# pc_sensything_v1.net
KiCad netlist of a schematic drawn in EAGLE
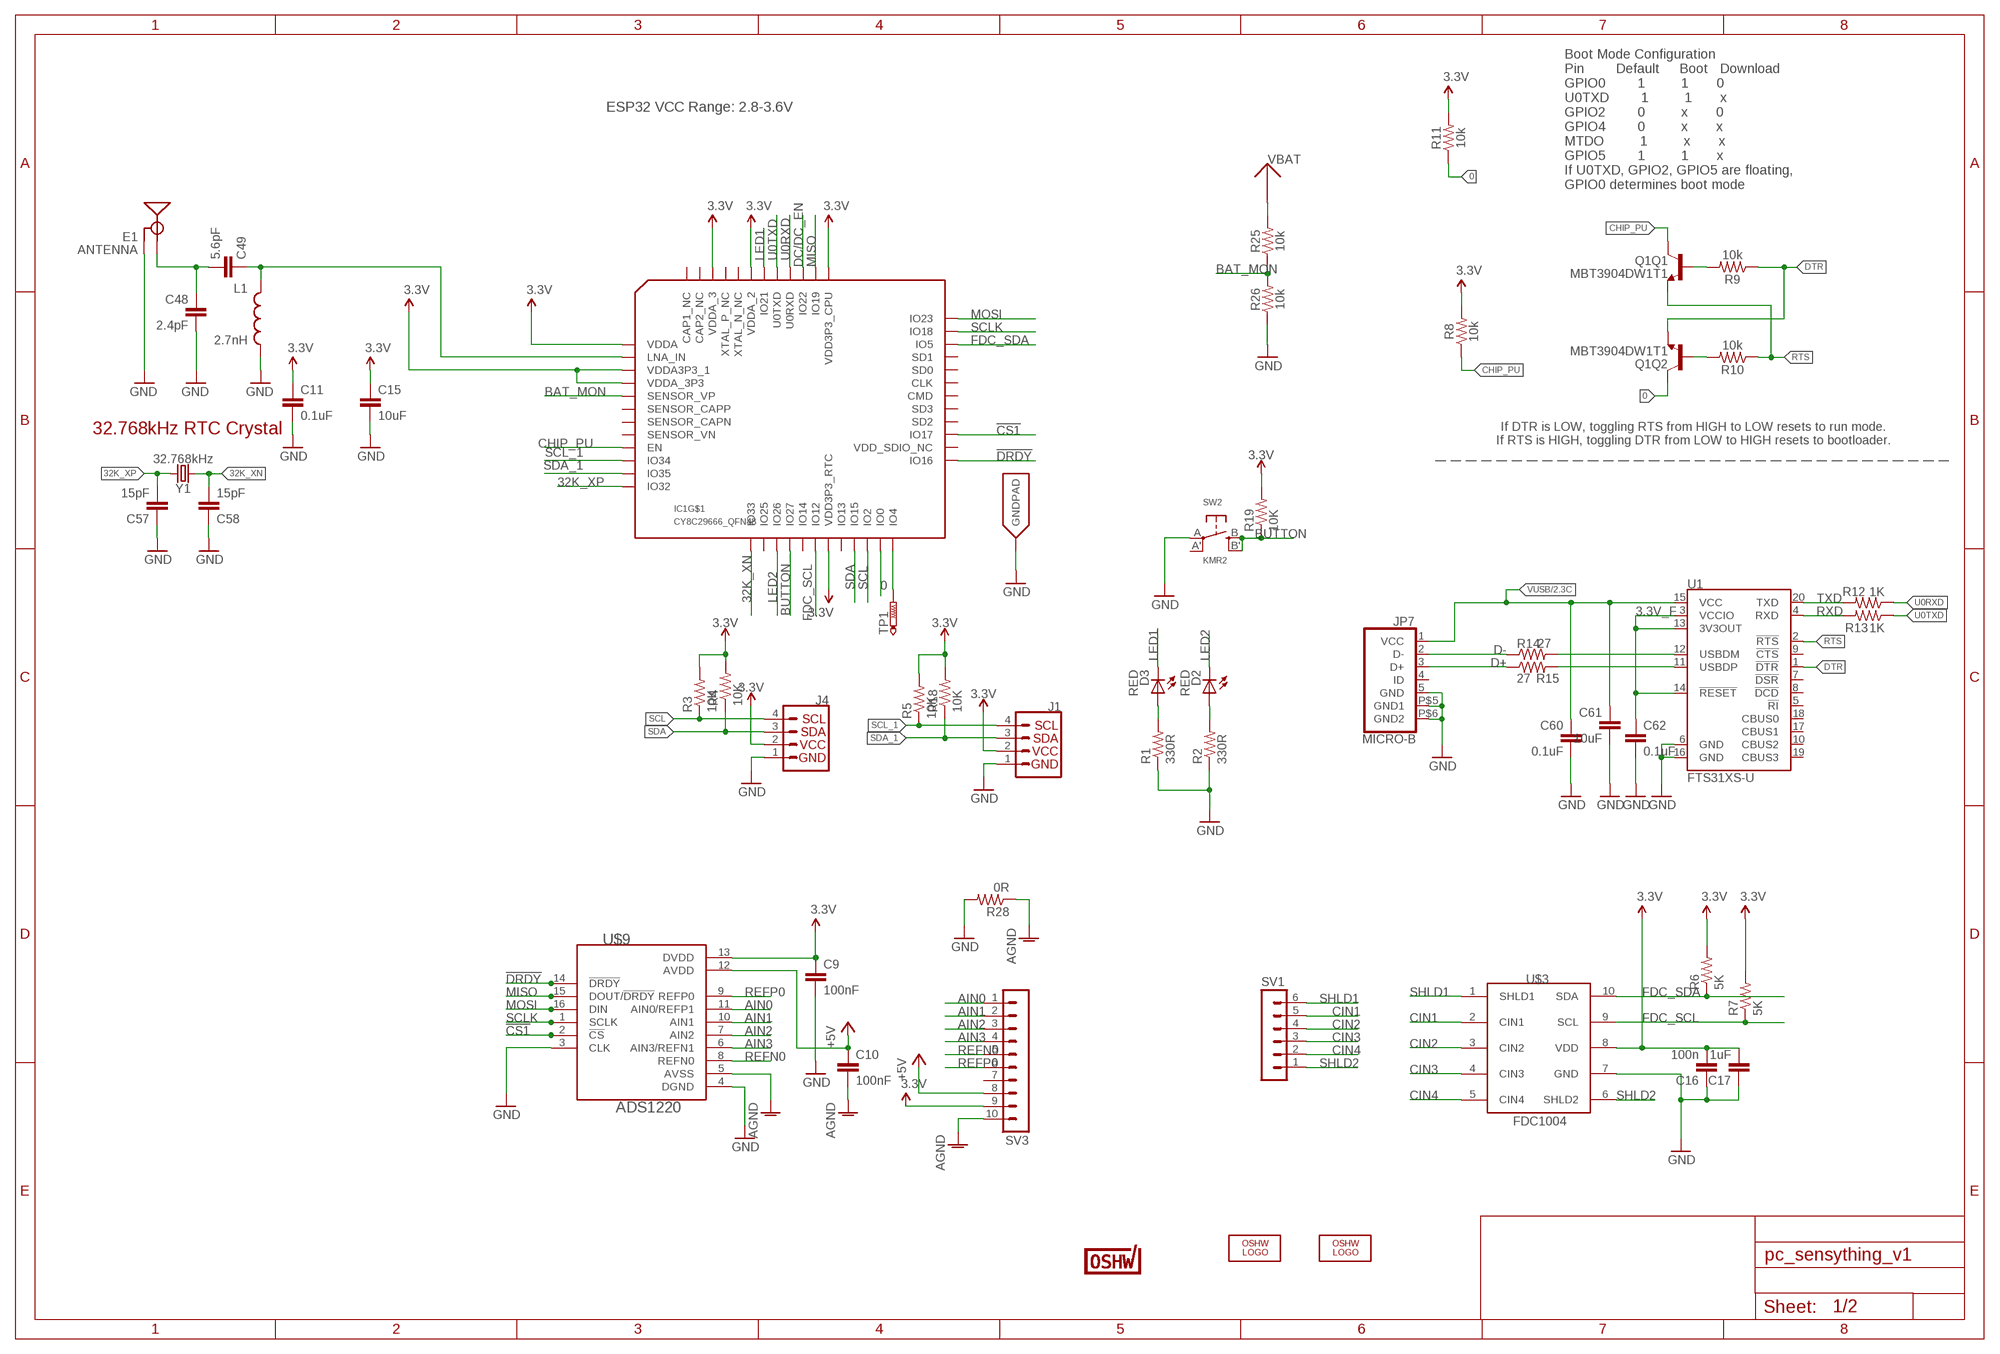
[diagram p0: schematic, sheet 1]
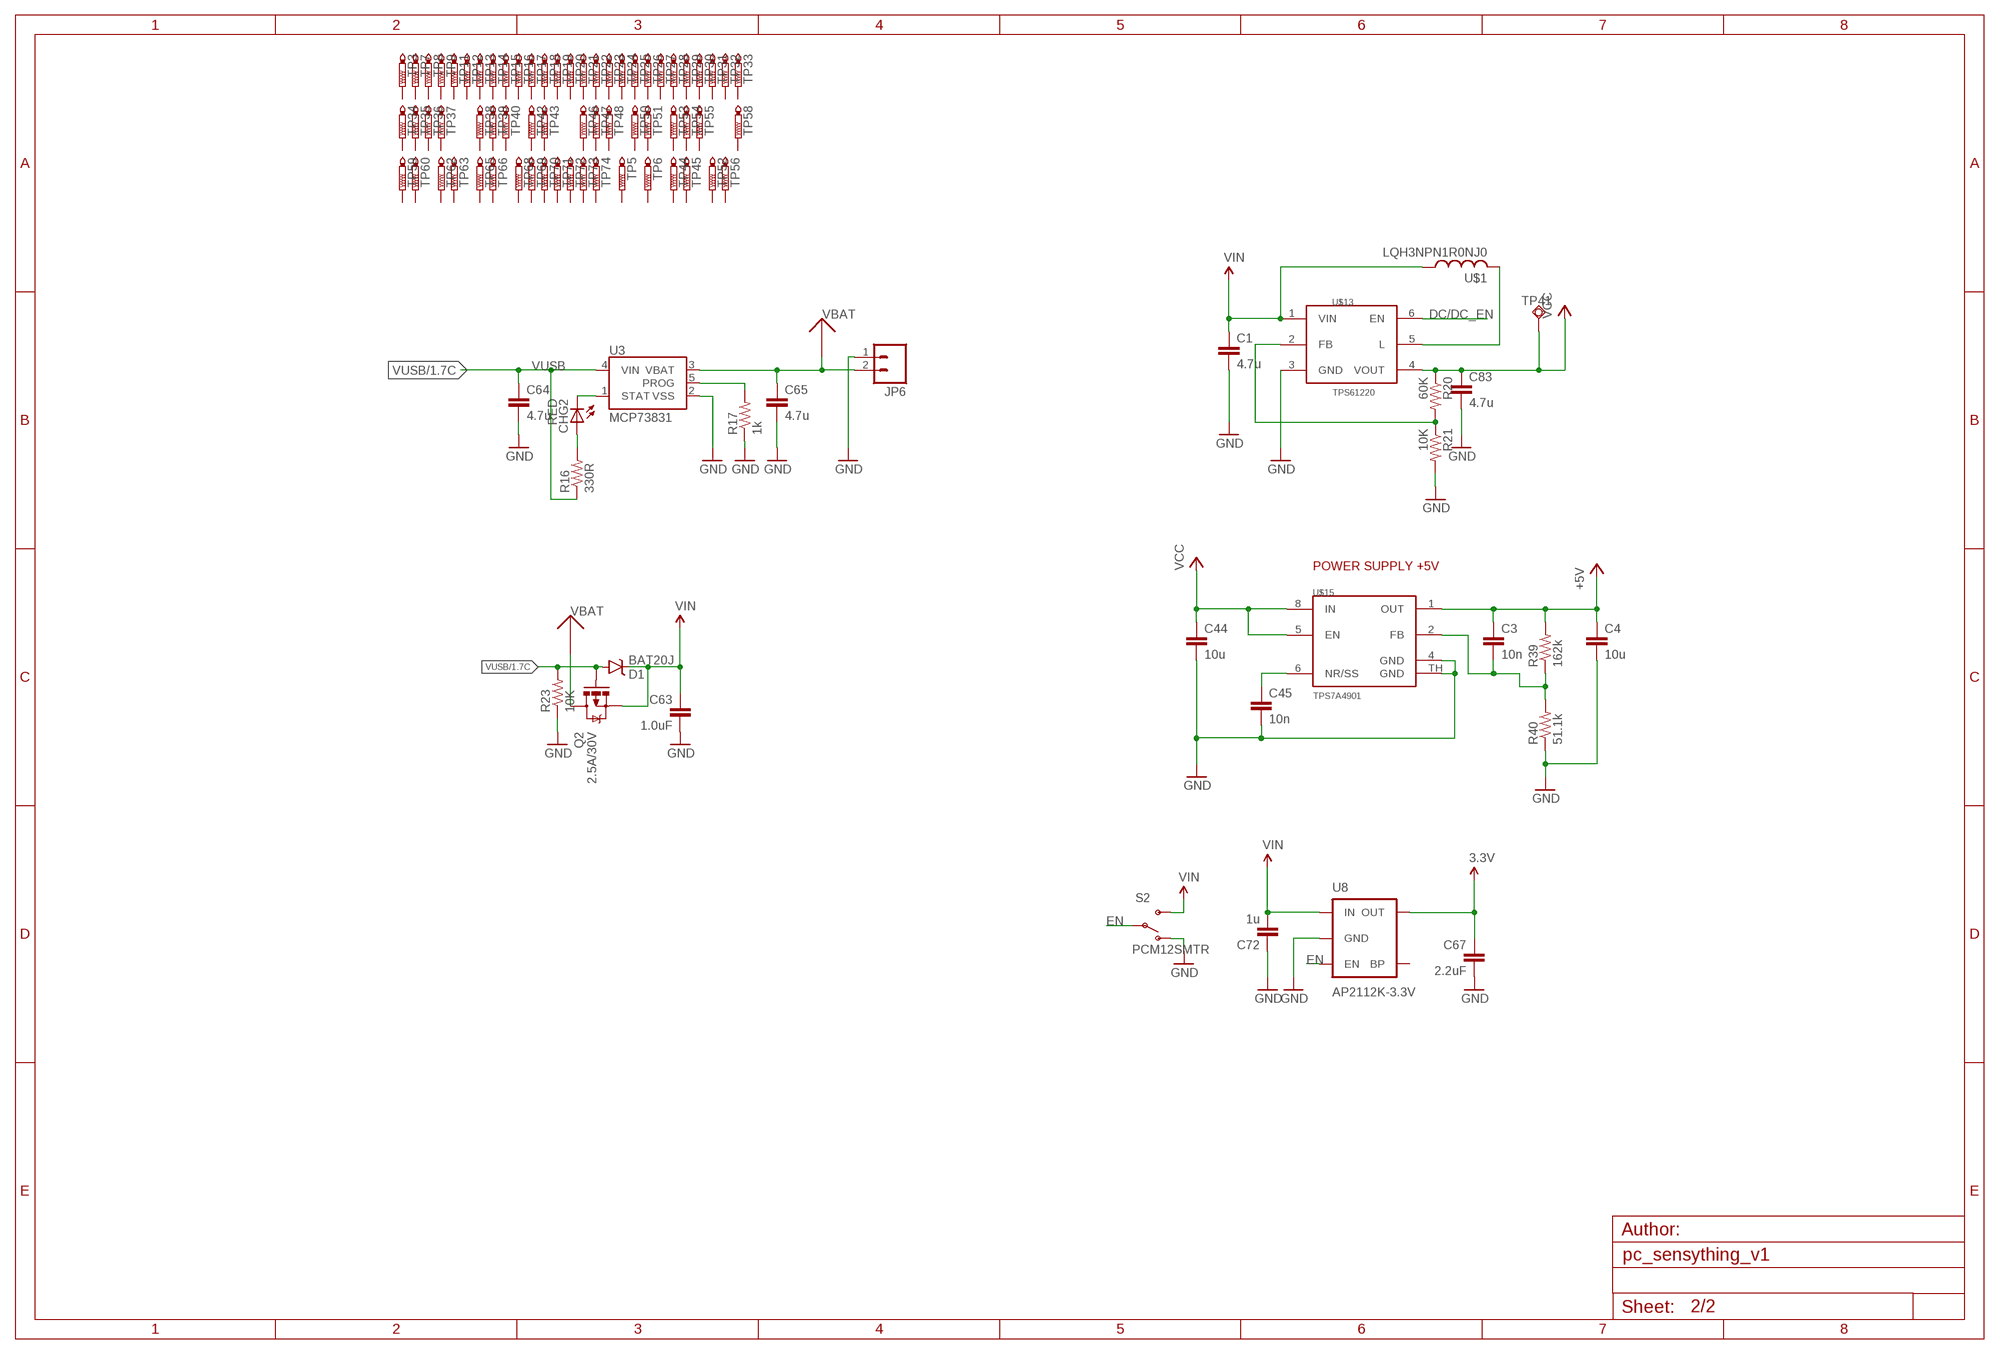
[diagram p1: schematic, sheet 2]

(export (version "E")
  (design (tool "Eeschema 10.0.6"))
  (components
    (comp (ref "C1")
      (value "4.7u")
      (footprint "eagle-import:C0805")
      (libsource (lib "eagle-import") (part "C-EUC0805"))
    )
    (comp (ref "C3")
      (value "10n")
      (footprint "eagle-import:C0402")
      (libsource (lib "eagle-import") (part "C-EUC0402"))
    )
    (comp (ref "C4")
      (value "10u")
      (footprint "eagle-import:C0805")
      (libsource (lib "eagle-import") (part "C-EUC0805"))
    )
    (comp (ref "C44")
      (value "10u")
      (footprint "eagle-import:C0805")
      (libsource (lib "eagle-import") (part "C-EUC0805"))
    )
    (comp (ref "C45")
      (value "10n")
      (footprint "eagle-import:C0402")
      (libsource (lib "eagle-import") (part "C-EUC0402"))
    )
    (comp (ref "C63")
      (value "1.0uF")
      (footprint "eagle-import:C0402")
      (libsource (lib "eagle-import") (part "C-EUC0402"))
    )
    (comp (ref "C64")
      (value "4.7u")
      (footprint "eagle-import:C0805")
      (libsource (lib "eagle-import") (part "C-EUC0805"))
    )
    (comp (ref "C65")
      (value "4.7u")
      (footprint "eagle-import:C0805")
      (libsource (lib "eagle-import") (part "C-EUC0805"))
    )
    (comp (ref "C67")
      (value "2.2uF")
      (footprint "eagle-import:C0402")
      (libsource (lib "eagle-import") (part "C-EUC0402"))
    )
    (comp (ref "C72")
      (value "1u")
      (footprint "eagle-import:C0402")
      (libsource (lib "eagle-import") (part "C-EUC0402"))
    )
    (comp (ref "C83")
      (value "4.7u")
      (footprint "eagle-import:C0805")
      (libsource (lib "eagle-import") (part "C-EUC0805"))
    )
    (comp (ref "CHG2")
      (value "RED")
      (footprint "eagle-import:CHIPLED_0603")
      (libsource (lib "eagle-import") (part "LEDCHIPLED_0603"))
    )
    (comp (ref "D1")
      (value "BAT20J")
      (footprint "eagle-import:SOD-323")
      (libsource (lib "eagle-import") (part "DIODE-SCHOTTKY-BAT20J"))
    )
    (comp (ref "JP6")
      (value "M02-JST-2MM-SMT")
      (footprint "eagle-import:JST-2-SMD")
      (libsource (lib "eagle-import") (part "M02-JST-2MM-SMT"))
    )
    (comp (ref "Q2")
      (value "2.5A/30V")
      (footprint "eagle-import:SOT23-3")
      (libsource (lib "eagle-import") (part "MOSFET-PCHANNELDMG2307L"))
    )
    (comp (ref "R16")
      (value "330R")
      (footprint "eagle-import:R0402")
      (libsource (lib "eagle-import") (part "R-US_R0402"))
    )
    (comp (ref "R17")
      (value "1k")
      (footprint "eagle-import:R0402")
      (libsource (lib "eagle-import") (part "R-US_R0402"))
    )
    (comp (ref "R20")
      (value "60K")
      (footprint "eagle-import:R0805")
      (libsource (lib "eagle-import") (part "R-US_R0805"))
    )
    (comp (ref "R21")
      (value "10K")
      (footprint "eagle-import:R0805")
      (libsource (lib "eagle-import") (part "R-US_R0805"))
    )
    (comp (ref "R23")
      (value "10K")
      (footprint "eagle-import:R0402")
      (libsource (lib "eagle-import") (part "R-US_R0402"))
    )
    (comp (ref "R39")
      (value "162k")
      (footprint "eagle-import:R0805")
      (libsource (lib "eagle-import") (part "R-US_R0805"))
    )
    (comp (ref "R40")
      (value "51.1k")
      (footprint "eagle-import:R0805")
      (libsource (lib "eagle-import") (part "R-US_R0805"))
    )
    (comp (ref "S2")
      (value "PCM12SMTR")
      (footprint "eagle-import:SWITCH-SPST-SMD-A")
      (libsource (lib "eagle-import") (part "SWITCH-SPDT-SMD-A"))
    )
    (comp (ref "TP3")
      (value "PTR1PAD1-13")
      (footprint "eagle-import:P1-13")
      (libsource (lib "eagle-import") (part "PTR1PAD1-13"))
    )
    (comp (ref "TP5")
      (value "PTR1PAD1-13")
      (footprint "eagle-import:P1-13")
      (libsource (lib "eagle-import") (part "PTR1PAD1-13"))
    )
    (comp (ref "TP6")
      (value "PTR1PAD1-13")
      (footprint "eagle-import:P1-13")
      (libsource (lib "eagle-import") (part "PTR1PAD1-13"))
    )
    (comp (ref "TP7")
      (value "PTR1PAD1-13")
      (footprint "eagle-import:P1-13")
      (libsource (lib "eagle-import") (part "PTR1PAD1-13"))
    )
    (comp (ref "TP8")
      (value "PTR1PAD1-13")
      (footprint "eagle-import:P1-13")
      (libsource (lib "eagle-import") (part "PTR1PAD1-13"))
    )
    (comp (ref "TP9")
      (value "PTR1PAD1-13")
      (footprint "eagle-import:P1-13")
      (libsource (lib "eagle-import") (part "PTR1PAD1-13"))
    )
    (comp (ref "TP11")
      (value "PTR1PAD1-13")
      (footprint "eagle-import:P1-13")
      (libsource (lib "eagle-import") (part "PTR1PAD1-13"))
    )
    (comp (ref "TP12")
      (value "PTR1PAD1-13")
      (footprint "eagle-import:P1-13")
      (libsource (lib "eagle-import") (part "PTR1PAD1-13"))
    )
    (comp (ref "TP13")
      (value "PTR1PAD1-13")
      (footprint "eagle-import:P1-13")
      (libsource (lib "eagle-import") (part "PTR1PAD1-13"))
    )
    (comp (ref "TP14")
      (value "PTR1PAD1-13")
      (footprint "eagle-import:P1-13")
      (libsource (lib "eagle-import") (part "PTR1PAD1-13"))
    )
    (comp (ref "TP15")
      (value "PTR1PAD1-13")
      (footprint "eagle-import:P1-13")
      (libsource (lib "eagle-import") (part "PTR1PAD1-13"))
    )
    (comp (ref "TP16")
      (value "PTR1PAD1-13")
      (footprint "eagle-import:P1-13")
      (libsource (lib "eagle-import") (part "PTR1PAD1-13"))
    )
    (comp (ref "TP17")
      (value "PTR1PAD1-13")
      (footprint "eagle-import:P1-13")
      (libsource (lib "eagle-import") (part "PTR1PAD1-13"))
    )
    (comp (ref "TP18")
      (value "PTR1PAD1-13")
      (footprint "eagle-import:P1-13")
      (libsource (lib "eagle-import") (part "PTR1PAD1-13"))
    )
    (comp (ref "TP19")
      (value "PTR1PAD1-13")
      (footprint "eagle-import:P1-13")
      (libsource (lib "eagle-import") (part "PTR1PAD1-13"))
    )
    (comp (ref "TP20")
      (value "PTR1PAD1-13")
      (footprint "eagle-import:P1-13")
      (libsource (lib "eagle-import") (part "PTR1PAD1-13"))
    )
    (comp (ref "TP21")
      (value "PTR1PAD1-13")
      (footprint "eagle-import:P1-13")
      (libsource (lib "eagle-import") (part "PTR1PAD1-13"))
    )
    (comp (ref "TP22")
      (value "PTR1PAD1-13")
      (footprint "eagle-import:P1-13")
      (libsource (lib "eagle-import") (part "PTR1PAD1-13"))
    )
    (comp (ref "TP23")
      (value "PTR1PAD1-13")
      (footprint "eagle-import:P1-13")
      (libsource (lib "eagle-import") (part "PTR1PAD1-13"))
    )
    (comp (ref "TP24")
      (value "PTR1PAD1-13")
      (footprint "eagle-import:P1-13")
      (libsource (lib "eagle-import") (part "PTR1PAD1-13"))
    )
    (comp (ref "TP25")
      (value "PTR1PAD1-13")
      (footprint "eagle-import:P1-13")
      (libsource (lib "eagle-import") (part "PTR1PAD1-13"))
    )
    (comp (ref "TP26")
      (value "PTR1PAD1-13")
      (footprint "eagle-import:P1-13")
      (libsource (lib "eagle-import") (part "PTR1PAD1-13"))
    )
    (comp (ref "TP27")
      (value "PTR1PAD1-13")
      (footprint "eagle-import:P1-13")
      (libsource (lib "eagle-import") (part "PTR1PAD1-13"))
    )
    (comp (ref "TP28")
      (value "PTR1PAD1-13")
      (footprint "eagle-import:P1-13")
      (libsource (lib "eagle-import") (part "PTR1PAD1-13"))
    )
    (comp (ref "TP29")
      (value "PTR1PAD1-13")
      (footprint "eagle-import:P1-13")
      (libsource (lib "eagle-import") (part "PTR1PAD1-13"))
    )
    (comp (ref "TP30")
      (value "PTR1PAD1-13")
      (footprint "eagle-import:P1-13")
      (libsource (lib "eagle-import") (part "PTR1PAD1-13"))
    )
    (comp (ref "TP31")
      (value "PTR1PAD1-13")
      (footprint "eagle-import:P1-13")
      (libsource (lib "eagle-import") (part "PTR1PAD1-13"))
    )
    (comp (ref "TP32")
      (value "PTR1PAD1-13")
      (footprint "eagle-import:P1-13")
      (libsource (lib "eagle-import") (part "PTR1PAD1-13"))
    )
    (comp (ref "TP33")
      (value "PTR1PAD1-13")
      (footprint "eagle-import:P1-13")
      (libsource (lib "eagle-import") (part "PTR1PAD1-13"))
    )
    (comp (ref "TP34")
      (value "PTR1PAD1-13")
      (footprint "eagle-import:P1-13")
      (libsource (lib "eagle-import") (part "PTR1PAD1-13"))
    )
    (comp (ref "TP35")
      (value "PTR1PAD1-13")
      (footprint "eagle-import:P1-13")
      (libsource (lib "eagle-import") (part "PTR1PAD1-13"))
    )
    (comp (ref "TP36")
      (value "PTR1PAD1-13")
      (footprint "eagle-import:P1-13")
      (libsource (lib "eagle-import") (part "PTR1PAD1-13"))
    )
    (comp (ref "TP37")
      (value "PTR1PAD1-13")
      (footprint "eagle-import:P1-13")
      (libsource (lib "eagle-import") (part "PTR1PAD1-13"))
    )
    (comp (ref "TP38")
      (value "PTR1PAD1-13")
      (footprint "eagle-import:P1-13")
      (libsource (lib "eagle-import") (part "PTR1PAD1-13"))
    )
    (comp (ref "TP39")
      (value "PTR1PAD1-13")
      (footprint "eagle-import:P1-13")
      (libsource (lib "eagle-import") (part "PTR1PAD1-13"))
    )
    (comp (ref "TP40")
      (value "PTR1PAD1-13")
      (footprint "eagle-import:P1-13")
      (libsource (lib "eagle-import") (part "PTR1PAD1-13"))
    )
    (comp (ref "TP41")
      (value "TPSQB1,27")
      (footprint "eagle-import:B1,27")
      (libsource (lib "eagle-import") (part "TPSQB1,27"))
    )
    (comp (ref "TP42")
      (value "PTR1PAD1-13")
      (footprint "eagle-import:P1-13")
      (libsource (lib "eagle-import") (part "PTR1PAD1-13"))
    )
    (comp (ref "TP43")
      (value "PTR1PAD1-13")
      (footprint "eagle-import:P1-13")
      (libsource (lib "eagle-import") (part "PTR1PAD1-13"))
    )
    (comp (ref "TP44")
      (value "PTR1PAD1-13")
      (footprint "eagle-import:P1-13")
      (libsource (lib "eagle-import") (part "PTR1PAD1-13"))
    )
    (comp (ref "TP45")
      (value "PTR1PAD1-13")
      (footprint "eagle-import:P1-13")
      (libsource (lib "eagle-import") (part "PTR1PAD1-13"))
    )
    (comp (ref "TP46")
      (value "PTR1PAD1-13")
      (footprint "eagle-import:P1-13")
      (libsource (lib "eagle-import") (part "PTR1PAD1-13"))
    )
    (comp (ref "TP47")
      (value "PTR1PAD1-13")
      (footprint "eagle-import:P1-13")
      (libsource (lib "eagle-import") (part "PTR1PAD1-13"))
    )
    (comp (ref "TP48")
      (value "PTR1PAD1-13")
      (footprint "eagle-import:P1-13")
      (libsource (lib "eagle-import") (part "PTR1PAD1-13"))
    )
    (comp (ref "TP50")
      (value "PTR1PAD1-13")
      (footprint "eagle-import:P1-13")
      (libsource (lib "eagle-import") (part "PTR1PAD1-13"))
    )
    (comp (ref "TP51")
      (value "PTR1PAD1-13")
      (footprint "eagle-import:P1-13")
      (libsource (lib "eagle-import") (part "PTR1PAD1-13"))
    )
    (comp (ref "TP52")
      (value "PTR1PAD1-13")
      (footprint "eagle-import:P1-13")
      (libsource (lib "eagle-import") (part "PTR1PAD1-13"))
    )
    (comp (ref "TP53")
      (value "PTR1PAD1-13")
      (footprint "eagle-import:P1-13")
      (libsource (lib "eagle-import") (part "PTR1PAD1-13"))
    )
    (comp (ref "TP54")
      (value "PTR1PAD1-13")
      (footprint "eagle-import:P1-13")
      (libsource (lib "eagle-import") (part "PTR1PAD1-13"))
    )
    (comp (ref "TP55")
      (value "PTR1PAD1-13")
      (footprint "eagle-import:P1-13")
      (libsource (lib "eagle-import") (part "PTR1PAD1-13"))
    )
    (comp (ref "TP56")
      (value "PTR1PAD1-13")
      (footprint "eagle-import:P1-13")
      (libsource (lib "eagle-import") (part "PTR1PAD1-13"))
    )
    (comp (ref "TP58")
      (value "PTR1PAD1-13")
      (footprint "eagle-import:P1-13")
      (libsource (lib "eagle-import") (part "PTR1PAD1-13"))
    )
    (comp (ref "TP59")
      (value "PTR1PAD1-13")
      (footprint "eagle-import:P1-13")
      (libsource (lib "eagle-import") (part "PTR1PAD1-13"))
    )
    (comp (ref "TP60")
      (value "PTR1PAD1-13")
      (footprint "eagle-import:P1-13")
      (libsource (lib "eagle-import") (part "PTR1PAD1-13"))
    )
    (comp (ref "TP62")
      (value "PTR1PAD1-13")
      (footprint "eagle-import:P1-13")
      (libsource (lib "eagle-import") (part "PTR1PAD1-13"))
    )
    (comp (ref "TP63")
      (value "PTR1PAD1-13")
      (footprint "eagle-import:P1-13")
      (libsource (lib "eagle-import") (part "PTR1PAD1-13"))
    )
    (comp (ref "TP65")
      (value "PTR1PAD1-13")
      (footprint "eagle-import:P1-13")
      (libsource (lib "eagle-import") (part "PTR1PAD1-13"))
    )
    (comp (ref "TP66")
      (value "PTR1PAD1-13")
      (footprint "eagle-import:P1-13")
      (libsource (lib "eagle-import") (part "PTR1PAD1-13"))
    )
    (comp (ref "TP68")
      (value "PTR1PAD1-13")
      (footprint "eagle-import:P1-13")
      (libsource (lib "eagle-import") (part "PTR1PAD1-13"))
    )
    (comp (ref "TP69")
      (value "PTR1PAD1-13")
      (footprint "eagle-import:P1-13")
      (libsource (lib "eagle-import") (part "PTR1PAD1-13"))
    )
    (comp (ref "TP70")
      (value "PTR1PAD1-13")
      (footprint "eagle-import:P1-13")
      (libsource (lib "eagle-import") (part "PTR1PAD1-13"))
    )
    (comp (ref "TP71")
      (value "PTR1PAD1-13")
      (footprint "eagle-import:P1-13")
      (libsource (lib "eagle-import") (part "PTR1PAD1-13"))
    )
    (comp (ref "TP72")
      (value "PTR1PAD1-13")
      (footprint "eagle-import:P1-13")
      (libsource (lib "eagle-import") (part "PTR1PAD1-13"))
    )
    (comp (ref "TP73")
      (value "PTR1PAD1-13")
      (footprint "eagle-import:P1-13")
      (libsource (lib "eagle-import") (part "PTR1PAD1-13"))
    )
    (comp (ref "TP74")
      (value "PTR1PAD1-13")
      (footprint "eagle-import:P1-13")
      (libsource (lib "eagle-import") (part "PTR1PAD1-13"))
    )
    (comp (ref "U$1")
      (value "LQH3NPN1R0NJ0")
      (footprint "eagle-import:LQH3NP")
      (libsource (lib "eagle-import") (part "LQH3NPN1R0NJ0"))
    )
    (comp (ref "U$13")
      (value "TPS61220")
      (footprint "eagle-import:SC-70-6")
      (libsource (lib "eagle-import") (part "TPS61222"))
    )
    (comp (ref "U$15")
      (value "TPS7A4901")
      (footprint "eagle-import:S-PDSO-G08")
      (libsource (lib "eagle-import") (part "TPS7A4901"))
    )
    (comp (ref "U3")
      (value "MCP73831")
      (footprint "eagle-import:SOT23-5")
      (libsource (lib "eagle-import") (part "MCP73831"))
    )
    (comp (ref "U8")
      (value "AP2112K-3.3V")
      (footprint "eagle-import:SOT23-5")
      (libsource (lib "eagle-import") (part "V_REG_LDOSMD"))
    )
    (comp (ref "C9")
      (value "100nF")
      (footprint "eagle-import:C0805")
      (libsource (lib "eagle-import") (part "C-EUC0805"))
    )
    (comp (ref "C10")
      (value "100nF")
      (footprint "eagle-import:C0805")
      (libsource (lib "eagle-import") (part "C-EUC0805"))
    )
    (comp (ref "C11")
      (value "0.1uF")
      (footprint "eagle-import:0603")
      (libsource (lib "eagle-import") (part "0.1UF-0603-25V-(+80/-20%)"))
    )
    (comp (ref "C15")
      (value "10uF")
      (footprint "eagle-import:0603")
      (libsource (lib "eagle-import") (part "10UF-0603-6.3V-20%"))
    )
    (comp (ref "C16")
      (value "100n")
      (footprint "eagle-import:C0805")
      (libsource (lib "eagle-import") (part "C-EUC0805"))
    )
    (comp (ref "C17")
      (value "1uF")
      (footprint "eagle-import:C0805")
      (libsource (lib "eagle-import") (part "C-EUC0805"))
    )
    (comp (ref "C48")
      (value "2.4pF")
      (footprint "eagle-import:0603")
      (libsource (lib "eagle-import") (part "2.4PF-0603-50V-5%"))
    )
    (comp (ref "C49")
      (value "5.6pF")
      (footprint "eagle-import:0603")
      (libsource (lib "eagle-import") (part "5.6PF-50V-5%(0603)"))
    )
    (comp (ref "C57")
      (value "15pF")
      (footprint "eagle-import:0603")
      (libsource (lib "eagle-import") (part "15PF-0603-50V-5%"))
    )
    (comp (ref "C58")
      (value "15pF")
      (footprint "eagle-import:0603")
      (libsource (lib "eagle-import") (part "15PF-0603-50V-5%"))
    )
    (comp (ref "C60")
      (value "0.1uF")
      (footprint "eagle-import:C0402")
      (libsource (lib "eagle-import") (part "C-EUC0402"))
    )
    (comp (ref "C61")
      (value "10uF")
      (footprint "eagle-import:C0805")
      (libsource (lib "eagle-import") (part "C-EUC0805"))
    )
    (comp (ref "C62")
      (value "0.1uF")
      (footprint "eagle-import:C0402")
      (libsource (lib "eagle-import") (part "C-EUC0402"))
    )
    (comp (ref "D2")
      (value "RED")
      (footprint "eagle-import:CHIPLED_0603")
      (libsource (lib "eagle-import") (part "LEDCHIPLED_0603"))
    )
    (comp (ref "D3")
      (value "RED")
      (footprint "eagle-import:CHIPLED_0603")
      (libsource (lib "eagle-import") (part "LEDCHIPLED_0603"))
    )
    (comp (ref "E1")
      (value "ANTENNA")
      (footprint "eagle-import:TRACE_ANTENNA_2.4GHZ_25.7MM_TUNED")
      (libsource (lib "eagle-import") (part "ANTENNATRACE-TUNED"))
    )
    (comp (ref "IC1")
      (value "CY8C29666_QFN48")
      (footprint "eagle-import:QFN48")
      (libsource (lib "eagle-import") (part "CY8C29666_QFN48"))
    )
    (comp (ref "J1")
      (value "QWIIC_CONNECTORJS-1MM")
      (footprint "eagle-import:1X04_1MM_RA")
      (libsource (lib "eagle-import") (part "QWIIC_CONNECTORJS-1MM"))
    )
    (comp (ref "J4")
      (value "QWIIC_CONNECTORJS-1MM")
      (footprint "eagle-import:1X04_1MM_RA")
      (libsource (lib "eagle-import") (part "QWIIC_CONNECTORJS-1MM"))
    )
    (comp (ref "JP7")
      (value "MICRO-B")
      (footprint "eagle-import:MICRO-B")
      (libsource (lib "eagle-import") (part "MICRO-B"))
    )
    (comp (ref "L1")
      (value "2.7nH")
      (footprint "eagle-import:0603")
      (libsource (lib "eagle-import") (part "INDUCTOR0603"))
    )
    (comp (ref "LOGO2")
      (value "OSHW_LOGO_FILLX0200-NT")
      (footprint "eagle-import:OSHW_FILLX200_NOTEXT")
      (libsource (lib "eagle-import") (part "OSHW_LOGO_FILLX0200-NT"))
    )
    (comp (ref "LOGO3")
      (value "OSHW_LOGO_FILLX0200-NT")
      (footprint "eagle-import:OSHW_FILLX200_NOTEXT")
      (libsource (lib "eagle-import") (part "OSHW_LOGO_FILLX0200-NT"))
    )
    (comp (ref "Q1")
      (value "MBT3904DW1T1")
      (footprint "eagle-import:SC70-6")
      (libsource (lib "eagle-import") (part "MBT3904DW1T1"))
    )
    (comp (ref "R1")
      (value "330R")
      (footprint "eagle-import:R0402")
      (libsource (lib "eagle-import") (part "R-US_R0402"))
    )
    (comp (ref "R2")
      (value "330R")
      (footprint "eagle-import:R0402")
      (libsource (lib "eagle-import") (part "R-US_R0402"))
    )
    (comp (ref "R3")
      (value "10K")
      (footprint "eagle-import:R0402")
      (libsource (lib "eagle-import") (part "R-US_R0402"))
    )
    (comp (ref "R4")
      (value "10K")
      (footprint "eagle-import:R0402")
      (libsource (lib "eagle-import") (part "R-US_R0402"))
    )
    (comp (ref "R5")
      (value "10K")
      (footprint "eagle-import:R0402")
      (libsource (lib "eagle-import") (part "R-US_R0402"))
    )
    (comp (ref "R6")
      (value "5K")
      (footprint "eagle-import:R0805")
      (libsource (lib "eagle-import") (part "R-US_R0805"))
    )
    (comp (ref "R7")
      (value "5K")
      (footprint "eagle-import:R0805")
      (libsource (lib "eagle-import") (part "R-US_R0805"))
    )
    (comp (ref "R8")
      (value "10k")
      (footprint "eagle-import:0603")
      (libsource (lib "eagle-import") (part "10KOHM-1/10W-1%(0603)0603"))
    )
    (comp (ref "R9")
      (value "10k")
      (footprint "eagle-import:0603")
      (libsource (lib "eagle-import") (part "10KOHM-0603-1/10W-1%"))
    )
    (comp (ref "R10")
      (value "10k")
      (footprint "eagle-import:0603")
      (libsource (lib "eagle-import") (part "10KOHM-0603-1/10W-1%"))
    )
    (comp (ref "R11")
      (value "10k")
      (footprint "eagle-import:0603")
      (libsource (lib "eagle-import") (part "10KOHM-1/10W-1%(0603)0603"))
    )
    (comp (ref "R12")
      (value "1K")
      (footprint "eagle-import:R0402")
      (libsource (lib "eagle-import") (part "R-US_R0402"))
    )
    (comp (ref "R13")
      (value "1K")
      (footprint "eagle-import:R0402")
      (libsource (lib "eagle-import") (part "R-US_R0402"))
    )
    (comp (ref "R14")
      (value "27")
      (footprint "eagle-import:R0402")
      (libsource (lib "eagle-import") (part "R-US_R0402"))
    )
    (comp (ref "R15")
      (value "27")
      (footprint "eagle-import:R0402")
      (libsource (lib "eagle-import") (part "R-US_R0402"))
    )
    (comp (ref "R18")
      (value "10K")
      (footprint "eagle-import:R0402")
      (libsource (lib "eagle-import") (part "R-US_R0402"))
    )
    (comp (ref "R19")
      (value "10K")
      (footprint "eagle-import:R0402")
      (libsource (lib "eagle-import") (part "R-US_R0402"))
    )
    (comp (ref "R25")
      (value "10k")
      (footprint "eagle-import:0603")
      (libsource (lib "eagle-import") (part "10KOHM-1/10W-1%(0603)0603"))
    )
    (comp (ref "R26")
      (value "10k")
      (footprint "eagle-import:0603")
      (libsource (lib "eagle-import") (part "10KOHM-1/10W-1%(0603)0603"))
    )
    (comp (ref "R28")
      (value "0R")
      (footprint "eagle-import:R0805")
      (libsource (lib "eagle-import") (part "R-US_R0805"))
    )
    (comp (ref "SV1")
      (value "MA06-1")
      (footprint "eagle-import:MA06-1")
      (libsource (lib "eagle-import") (part "MA06-1"))
    )
    (comp (ref "SV3")
      (value "MA10-1")
      (footprint "eagle-import:MA10-1")
      (libsource (lib "eagle-import") (part "MA10-1"))
    )
    (comp (ref "SW2")
      (value "KMR2")
      (footprint "eagle-import:BTN_KMR2_4.6X2.8")
      (libsource (lib "eagle-import") (part "SWITCH_TACT_SMT4.6X2.8"))
    )
    (comp (ref "TP1")
      (value "PTR1TP10SQ")
      (footprint "eagle-import:TP10SQ")
      (libsource (lib "eagle-import") (part "PTR1TP10SQ"))
    )
    (comp (ref "U$3")
      (value "FDC1004")
      (footprint "eagle-import:VSSOP-10")
      (libsource (lib "eagle-import") (part "FDC1004"))
    )
    (comp (ref "U$9")
      (value "ADS1220")
      (footprint "eagle-import:TSSOP-16")
      (libsource (lib "eagle-import") (part "ADS1220"))
    )
    (comp (ref "U$22")
      (value "CERT-SMALL")
      (footprint "eagle-import:CERT-SMALL-SILK")
      (libsource (lib "eagle-import") (part "CERT-SMALL"))
    )
    (comp (ref "U1")
      (value "FTS31XS-U")
      (footprint "eagle-import:SSOP20_L")
      (libsource (lib "eagle-import") (part "FT231XS"))
    )
    (comp (ref "Y1")
      (value "32.768kHz")
      (footprint "eagle-import:CRYSTAL-SMD-3.2X1.5MM")
      (libsource (lib "eagle-import") (part "CRYSTAL-32.768KHZSMD-3.2X1.5"))
    )
  )
  (nets
    (net (code "1") (name "+5V") (class "Default")
      (node (ref "C10") (pin "1") (pinfunction "1_1") (pintype "passive"))
      (node (ref "C3") (pin "1") (pinfunction "1_1") (pintype "passive"))
      (node (ref "C4") (pin "1") (pinfunction "1_1") (pintype "passive"))
      (node (ref "R39") (pin "2") (pinfunction "2_2") (pintype "passive"))
      (node (ref "SV3") (pin "8") (pinfunction "8_8") (pintype "passive"))
      (node (ref "U$15") (pin "1") (pinfunction "OUT_1") (pintype "bidirectional"))
      (node (ref "U$9") (pin "12") (pinfunction "AVDD_12") (pintype "bidirectional"))
    )
    (net (code "2") (name "0") (class "Default")
      (node (ref "IC1") (pin "23") (pinfunction "IO0_23") (pintype "bidirectional"))
      (node (ref "Q1") (pin "6") (pinfunction "C_6") (pintype "passive"))
      (node (ref "R11") (pin "1") (pinfunction "1_1") (pintype "passive"))
    )
    (net (code "3") (name "3.3V") (class "Default")
      (node (ref "C11") (pin "1") (pinfunction "1_1") (pintype "passive"))
      (node (ref "C15") (pin "1") (pinfunction "1_1") (pintype "passive"))
      (node (ref "C16") (pin "2") (pinfunction "2_2") (pintype "passive"))
      (node (ref "C17") (pin "2") (pinfunction "2_2") (pintype "passive"))
      (node (ref "C67") (pin "1") (pinfunction "1_1") (pintype "passive"))
      (node (ref "C9") (pin "1") (pinfunction "1_1") (pintype "passive"))
      (node (ref "IC1") (pin "1") (pinfunction "VDDA_1") (pintype "bidirectional"))
      (node (ref "IC1") (pin "19") (pinfunction "VDD3P3_RTC_19") (pintype "bidirectional"))
      (node (ref "IC1") (pin "3") (pinfunction "VDDA3P3_1_3") (pintype "bidirectional"))
      (node (ref "IC1") (pin "37") (pinfunction "VDD3P3_CPU_37") (pintype "bidirectional"))
      (node (ref "IC1") (pin "4") (pinfunction "VDDA_3P3_4") (pintype "bidirectional"))
      (node (ref "IC1") (pin "43") (pinfunction "VDDA_2_43") (pintype "bidirectional"))
      (node (ref "IC1") (pin "46") (pinfunction "VDDA_3_46") (pintype "bidirectional"))
      (node (ref "J1") (pin "2") (pinfunction "2_2") (pintype "power_in"))
      (node (ref "J4") (pin "2") (pinfunction "2_2") (pintype "power_in"))
      (node (ref "R11") (pin "2") (pinfunction "2_2") (pintype "passive"))
      (node (ref "R18") (pin "2") (pinfunction "2_2") (pintype "passive"))
      (node (ref "R19") (pin "2") (pinfunction "2_2") (pintype "passive"))
      (node (ref "R3") (pin "2") (pinfunction "2_2") (pintype "passive"))
      (node (ref "R4") (pin "2") (pinfunction "2_2") (pintype "passive"))
      (node (ref "R5") (pin "2") (pinfunction "2_2") (pintype "passive"))
      (node (ref "R6") (pin "2") (pinfunction "2_2") (pintype "passive"))
      (node (ref "R7") (pin "2") (pinfunction "2_2") (pintype "passive"))
      (node (ref "R8") (pin "2") (pinfunction "2_2") (pintype "passive"))
      (node (ref "SV3") (pin "9") (pinfunction "9_9") (pintype "passive"))
      (node (ref "U$3") (pin "8") (pinfunction "VDD_8") (pintype "bidirectional"))
      (node (ref "U$9") (pin "13") (pinfunction "DVDD_13") (pintype "bidirectional"))
      (node (ref "U8") (pin "5") (pinfunction "OUT_5") (pintype "passive"))
    )
    (net (code "4") (name "3.3V_F") (class "Default")
      (node (ref "C62") (pin "1") (pinfunction "1_1") (pintype "passive"))
      (node (ref "U1") (pin "13") (pinfunction "3V3OUT_13") (pintype "bidirectional"))
      (node (ref "U1") (pin "14") (pinfunction "~{RESET}_14") (pintype "bidirectional"))
      (node (ref "U1") (pin "3") (pinfunction "VCCIO_3") (pintype "bidirectional"))
    )
    (net (code "5") (name "32K_XN") (class "Default")
      (node (ref "C58") (pin "2") (pinfunction "2_2") (pintype "passive"))
      (node (ref "IC1") (pin "13") (pinfunction "IO33_13") (pintype "bidirectional"))
      (node (ref "Y1") (pin "P$2") (pinfunction "2_P$2") (pintype "passive"))
    )
    (net (code "6") (name "32K_XP") (class "Default")
      (node (ref "C57") (pin "2") (pinfunction "2_2") (pintype "passive"))
      (node (ref "IC1") (pin "12") (pinfunction "IO32_12") (pintype "bidirectional"))
      (node (ref "Y1") (pin "P$1") (pinfunction "1_P$1") (pintype "passive"))
    )
    (net (code "7") (name "AGND") (class "Default")
      (node (ref "C10") (pin "2") (pinfunction "2_2") (pintype "passive"))
      (node (ref "R28") (pin "1") (pinfunction "1_1") (pintype "passive"))
      (node (ref "SV3") (pin "10") (pinfunction "10_10") (pintype "passive"))
      (node (ref "U$9") (pin "5") (pinfunction "AVSS_5") (pintype "bidirectional"))
    )
    (net (code "8") (name "AIN0") (class "Default")
      (node (ref "SV3") (pin "1") (pinfunction "1_1") (pintype "passive"))
      (node (ref "U$9") (pin "11") (pinfunction "AIN0/REFP1_11") (pintype "bidirectional"))
    )
    (net (code "9") (name "AIN1") (class "Default")
      (node (ref "SV3") (pin "2") (pinfunction "2_2") (pintype "passive"))
      (node (ref "U$9") (pin "10") (pinfunction "AIN1_10") (pintype "bidirectional"))
    )
    (net (code "10") (name "AIN2") (class "Default")
      (node (ref "SV3") (pin "3") (pinfunction "3_3") (pintype "passive"))
      (node (ref "U$9") (pin "7") (pinfunction "AIN2_7") (pintype "bidirectional"))
    )
    (net (code "11") (name "AIN3") (class "Default")
      (node (ref "SV3") (pin "4") (pinfunction "4_4") (pintype "passive"))
      (node (ref "U$9") (pin "6") (pinfunction "AIN3/REFN1_6") (pintype "bidirectional"))
    )
    (net (code "12") (name "BAT_MON") (class "Default")
      (node (ref "IC1") (pin "5") (pinfunction "SENSOR_VP_5") (pintype "bidirectional"))
      (node (ref "R25") (pin "1") (pinfunction "1_1") (pintype "passive"))
      (node (ref "R26") (pin "2") (pinfunction "2_2") (pintype "passive"))
    )
    (net (code "13") (name "BUTTON") (class "Default")
      (node (ref "IC1") (pin "16") (pinfunction "IO27_16") (pintype "bidirectional"))
      (node (ref "R19") (pin "1") (pinfunction "1_1") (pintype "passive"))
      (node (ref "SW2") (pin "B") (pinfunction "S_B") (pintype "passive"))
      (node (ref "SW2") (pin "B'") (pinfunction "S1_B'") (pintype "passive"))
    )
    (net (code "14") (name "CHIP_PU") (class "Default")
      (node (ref "IC1") (pin "9") (pinfunction "EN_9") (pintype "bidirectional"))
      (node (ref "Q1") (pin "3") (pinfunction "C_3") (pintype "passive"))
      (node (ref "R8") (pin "1") (pinfunction "1_1") (pintype "passive"))
    )
    (net (code "15") (name "CIN1") (class "Default")
      (node (ref "SV1") (pin "5") (pinfunction "5_5") (pintype "passive"))
      (node (ref "U$3") (pin "2") (pinfunction "CIN1_2") (pintype "bidirectional"))
    )
    (net (code "16") (name "CIN2") (class "Default")
      (node (ref "SV1") (pin "4") (pinfunction "4_4") (pintype "passive"))
      (node (ref "U$3") (pin "3") (pinfunction "CIN2_3") (pintype "bidirectional"))
    )
    (net (code "17") (name "CIN3") (class "Default")
      (node (ref "SV1") (pin "3") (pinfunction "3_3") (pintype "passive"))
      (node (ref "U$3") (pin "4") (pinfunction "CIN3_4") (pintype "bidirectional"))
    )
    (net (code "18") (name "CIN4") (class "Default")
      (node (ref "SV1") (pin "2") (pinfunction "2_2") (pintype "passive"))
      (node (ref "U$3") (pin "5") (pinfunction "CIN4_5") (pintype "bidirectional"))
    )
    (net (code "19") (name "D+") (class "Default")
      (node (ref "JP7") (pin "3") (pinfunction "D+_3") (pintype "bidirectional"))
      (node (ref "R15") (pin "1") (pinfunction "1_1") (pintype "passive"))
    )
    (net (code "20") (name "D-") (class "Default")
      (node (ref "JP7") (pin "2") (pinfunction "D-_2") (pintype "bidirectional"))
      (node (ref "R14") (pin "1") (pinfunction "1_1") (pintype "passive"))
    )
    (net (code "21") (name "DC{slash}DC_EN") (class "Default")
      (node (ref "IC1") (pin "39") (pinfunction "IO22_39") (pintype "bidirectional"))
      (node (ref "U$13") (pin "6") (pinfunction "EN_6") (pintype "bidirectional"))
    )
    (net (code "22") (name "DTR") (class "Default")
      (node (ref "Q1") (pin "1") (pinfunction "E_1") (pintype "passive"))
      (node (ref "R9") (pin "1") (pinfunction "1_1") (pintype "passive"))
      (node (ref "U1") (pin "1") (pinfunction "~{DTR}_1") (pintype "bidirectional"))
    )
    (net (code "23") (name "EN") (class "Default")
      (node (ref "S2") (pin "2") (pinfunction "P_2") (pintype "passive"))
      (node (ref "U8") (pin "3") (pinfunction "EN_3") (pintype "input"))
    )
    (net (code "24") (name "FDC_SCL") (class "Default")
      (node (ref "IC1") (pin "18") (pinfunction "IO12_18") (pintype "power_in"))
      (node (ref "R7") (pin "1") (pinfunction "1_1") (pintype "passive"))
      (node (ref "U$3") (pin "9") (pinfunction "SCL_9") (pintype "bidirectional"))
    )
    (net (code "25") (name "FDC_SDA") (class "Default")
      (node (ref "IC1") (pin "34") (pinfunction "IO5_34") (pintype "bidirectional"))
      (node (ref "R6") (pin "1") (pinfunction "1_1") (pintype "passive"))
      (node (ref "U$3") (pin "10") (pinfunction "SDA_10") (pintype "bidirectional"))
    )
    (net (code "26") (name "GND") (class "Default")
      (node (ref "C1") (pin "2") (pinfunction "2_2") (pintype "passive"))
      (node (ref "C11") (pin "2") (pinfunction "2_2") (pintype "passive"))
      (node (ref "C15") (pin "2") (pinfunction "2_2") (pintype "passive"))
      (node (ref "C16") (pin "1") (pinfunction "1_1") (pintype "passive"))
      (node (ref "C17") (pin "1") (pinfunction "1_1") (pintype "passive"))
      (node (ref "C4") (pin "2") (pinfunction "2_2") (pintype "passive"))
      (node (ref "C44") (pin "2") (pinfunction "2_2") (pintype "passive"))
      (node (ref "C45") (pin "2") (pinfunction "2_2") (pintype "passive"))
      (node (ref "C48") (pin "2") (pinfunction "2_2") (pintype "passive"))
      (node (ref "C57") (pin "1") (pinfunction "1_1") (pintype "passive"))
      (node (ref "C58") (pin "1") (pinfunction "1_1") (pintype "passive"))
      (node (ref "C60") (pin "2") (pinfunction "2_2") (pintype "passive"))
      (node (ref "C61") (pin "2") (pinfunction "2_2") (pintype "passive"))
      (node (ref "C62") (pin "2") (pinfunction "2_2") (pintype "passive"))
      (node (ref "C63") (pin "2") (pinfunction "2_2") (pintype "passive"))
      (node (ref "C64") (pin "2") (pinfunction "2_2") (pintype "passive"))
      (node (ref "C65") (pin "2") (pinfunction "2_2") (pintype "passive"))
      (node (ref "C67") (pin "2") (pinfunction "2_2") (pintype "passive"))
      (node (ref "C72") (pin "1") (pinfunction "1_1") (pintype "passive"))
      (node (ref "C83") (pin "2") (pinfunction "2_2") (pintype "passive"))
      (node (ref "C9") (pin "2") (pinfunction "2_2") (pintype "passive"))
      (node (ref "E1") (pin "GND") (pinfunction "GND_GND") (pintype "bidirectional"))
      (node (ref "E1") (pin "GND2") (pinfunction "GND_GND2") (pintype "bidirectional"))
      (node (ref "IC1") (pin "EXP") (pinfunction "GNDPAD_EXP") (pintype "power_in"))
      (node (ref "J1") (pin "1") (pinfunction "1_1") (pintype "power_in"))
      (node (ref "J4") (pin "1") (pinfunction "1_1") (pintype "power_in"))
      (node (ref "JP6") (pin "1") (pinfunction "1_1") (pintype "passive"))
      (node (ref "JP7") (pin "5") (pinfunction "GND_5") (pintype "bidirectional"))
      (node (ref "JP7") (pin "P$5") (pinfunction "GND1_P$5") (pintype "bidirectional"))
      (node (ref "JP7") (pin "P$6") (pinfunction "GND2_P$6") (pintype "bidirectional"))
      (node (ref "L1") (pin "2") (pinfunction "2_2") (pintype "passive"))
      (node (ref "R1") (pin "1") (pinfunction "1_1") (pintype "passive"))
      (node (ref "R17") (pin "1") (pinfunction "1_1") (pintype "passive"))
      (node (ref "R2") (pin "1") (pinfunction "1_1") (pintype "passive"))
      (node (ref "R21") (pin "2") (pinfunction "2_2") (pintype "passive"))
      (node (ref "R23") (pin "1") (pinfunction "1_1") (pintype "passive"))
      (node (ref "R26") (pin "1") (pinfunction "1_1") (pintype "passive"))
      (node (ref "R28") (pin "2") (pinfunction "2_2") (pintype "passive"))
      (node (ref "R40") (pin "1") (pinfunction "1_1") (pintype "passive"))
      (node (ref "S2") (pin "1") (pinfunction "O_1") (pintype "passive"))
      (node (ref "SW2") (pin "A") (pinfunction "P_A") (pintype "passive"))
      (node (ref "U$13") (pin "3") (pinfunction "GND_3") (pintype "bidirectional"))
      (node (ref "U$15") (pin "4") (pinfunction "GND_4") (pintype "bidirectional"))
      (node (ref "U$15") (pin "TH") (pinfunction "GND_TH") (pintype "bidirectional"))
      (node (ref "U$3") (pin "7") (pinfunction "GND_7") (pintype "bidirectional"))
      (node (ref "U$9") (pin "3") (pinfunction "CLK_3") (pintype "bidirectional"))
      (node (ref "U$9") (pin "4") (pinfunction "DGND_4") (pintype "bidirectional"))
      (node (ref "U1") (pin "16") (pinfunction "GND_16") (pintype "bidirectional"))
      (node (ref "U1") (pin "6") (pinfunction "GND_6") (pintype "bidirectional"))
      (node (ref "U3") (pin "2") (pinfunction "VSS_2") (pintype "power_in"))
      (node (ref "U8") (pin "2") (pinfunction "GND_2") (pintype "input"))
    )
    (net (code "27") (name "LED1") (class "Default")
      (node (ref "D3") (pin "C") (pinfunction "C_C") (pintype "passive"))
      (node (ref "IC1") (pin "42") (pinfunction "IO21_42") (pintype "power_in"))
    )
    (net (code "28") (name "LED2") (class "Default")
      (node (ref "D2") (pin "C") (pinfunction "C_C") (pintype "passive"))
      (node (ref "IC1") (pin "15") (pinfunction "IO26_15") (pintype "bidirectional"))
    )
    (net (code "29") (name "MISO") (class "Default")
      (node (ref "IC1") (pin "38") (pinfunction "IO19_38") (pintype "bidirectional"))
      (node (ref "U$9") (pin "15") (pinfunction "DOUT/~{DRDY}_15") (pintype "bidirectional"))
    )
    (net (code "30") (name "MOSI") (class "Default")
      (node (ref "IC1") (pin "36") (pinfunction "IO23_36") (pintype "bidirectional"))
      (node (ref "U$9") (pin "16") (pinfunction "DIN_16") (pintype "bidirectional"))
    )
    (net (code "31") (name "Net-(CHG2-PadA)") (class "Default")
      (node (ref "CHG2") (pin "A") (pinfunction "A_A") (pintype "passive"))
      (node (ref "R16") (pin "2") (pinfunction "2_2") (pintype "passive"))
    )
    (net (code "32") (name "Net-(D2-PadA)") (class "Default")
      (node (ref "D2") (pin "A") (pinfunction "A_A") (pintype "passive"))
      (node (ref "R2") (pin "2") (pinfunction "2_2") (pintype "passive"))
    )
    (net (code "33") (name "Net-(D3-PadA)") (class "Default")
      (node (ref "D3") (pin "A") (pinfunction "A_A") (pintype "passive"))
      (node (ref "R1") (pin "2") (pinfunction "2_2") (pintype "passive"))
    )
    (net (code "34") (name "Net-(E1-SIGNAL)") (class "Default")
      (node (ref "C48") (pin "1") (pinfunction "1_1") (pintype "passive"))
      (node (ref "C49") (pin "2") (pinfunction "2_2") (pintype "passive"))
      (node (ref "E1") (pin "ANT") (pinfunction "SIGNAL_ANT") (pintype "bidirectional"))
    )
    (net (code "35") (name "Net-(IC1A-IO4)") (class "Default")
      (node (ref "IC1") (pin "24") (pinfunction "IO4_24") (pintype "bidirectional"))
      (node (ref "TP1") (pin "TP") (pinfunction "TP_TP") (pintype "input"))
    )
    (net (code "36") (name "Net-(IC1A-LNA_IN)") (class "Default")
      (node (ref "C49") (pin "1") (pinfunction "1_1") (pintype "passive"))
      (node (ref "IC1") (pin "2") (pinfunction "LNA_IN_2") (pintype "bidirectional"))
      (node (ref "L1") (pin "1") (pinfunction "1_1") (pintype "passive"))
    )
    (net (code "37") (name "Net-(Q1A-B)") (class "Default")
      (node (ref "Q1") (pin "5") (pinfunction "B_5") (pintype "passive"))
      (node (ref "R9") (pin "2") (pinfunction "2_2") (pintype "passive"))
    )
    (net (code "38") (name "Net-(Q1B-B)") (class "Default")
      (node (ref "Q1") (pin "2") (pinfunction "B_2") (pintype "passive"))
      (node (ref "R10") (pin "2") (pinfunction "2_2") (pintype "passive"))
    )
    (net (code "39") (name "Net-(U$1-2)") (class "Default")
      (node (ref "U$1") (pin "P$2") (pinfunction "2_P$2") (pintype "passive"))
      (node (ref "U$13") (pin "5") (pinfunction "L_5") (pintype "bidirectional"))
    )
    (net (code "40") (name "Net-(U$13-FB)") (class "Default")
      (node (ref "R20") (pin "2") (pinfunction "2_2") (pintype "passive"))
      (node (ref "R21") (pin "1") (pinfunction "1_1") (pintype "passive"))
      (node (ref "U$13") (pin "2") (pinfunction "FB_2") (pintype "bidirectional"))
    )
    (net (code "41") (name "Net-(U$15-FB)") (class "Default")
      (node (ref "C3") (pin "2") (pinfunction "2_2") (pintype "passive"))
      (node (ref "R39") (pin "1") (pinfunction "1_1") (pintype "passive"))
      (node (ref "R40") (pin "2") (pinfunction "2_2") (pintype "passive"))
      (node (ref "U$15") (pin "2") (pinfunction "FB_2") (pintype "bidirectional"))
    )
    (net (code "42") (name "Net-(U$15-NR{slash}SS)") (class "Default")
      (node (ref "C45") (pin "1") (pinfunction "1_1") (pintype "passive"))
      (node (ref "U$15") (pin "6") (pinfunction "NR/SS_6") (pintype "bidirectional"))
    )
    (net (code "43") (name "Net-(U1-USBDM)") (class "Default")
      (node (ref "R14") (pin "2") (pinfunction "2_2") (pintype "passive"))
      (node (ref "U1") (pin "12") (pinfunction "USBDM_12") (pintype "bidirectional"))
    )
    (net (code "44") (name "Net-(U1-USBDP)") (class "Default")
      (node (ref "R15") (pin "2") (pinfunction "2_2") (pintype "passive"))
      (node (ref "U1") (pin "11") (pinfunction "USBDP_11") (pintype "bidirectional"))
    )
    (net (code "45") (name "Net-(U3-PROG)") (class "Default")
      (node (ref "R17") (pin "2") (pinfunction "2_2") (pintype "passive"))
      (node (ref "U3") (pin "5") (pinfunction "PROG_5") (pintype "input"))
    )
    (net (code "46") (name "Net-(U3-STAT)") (class "Default")
      (node (ref "CHG2") (pin "C") (pinfunction "C_C") (pintype "passive"))
      (node (ref "U3") (pin "1") (pinfunction "STAT_1") (pintype "output"))
    )
    (net (code "47") (name "REFN0") (class "Default")
      (node (ref "SV3") (pin "5") (pinfunction "5_5") (pintype "passive"))
      (node (ref "U$9") (pin "8") (pinfunction "REFN0_8") (pintype "bidirectional"))
    )
    (net (code "48") (name "REFP0") (class "Default")
      (node (ref "SV3") (pin "6") (pinfunction "6_6") (pintype "passive"))
      (node (ref "U$9") (pin "9") (pinfunction "REFP0_9") (pintype "bidirectional"))
    )
    (net (code "49") (name "RTS") (class "Default")
      (node (ref "Q1") (pin "4") (pinfunction "E_4") (pintype "passive"))
      (node (ref "R10") (pin "1") (pinfunction "1_1") (pintype "passive"))
      (node (ref "U1") (pin "2") (pinfunction "~{RTS}_2") (pintype "bidirectional"))
    )
    (net (code "50") (name "RXD") (class "Default")
      (node (ref "R13") (pin "2") (pinfunction "2_2") (pintype "passive"))
      (node (ref "U1") (pin "4") (pinfunction "RXD_4") (pintype "bidirectional"))
    )
    (net (code "51") (name "SCL") (class "Default")
      (node (ref "IC1") (pin "22") (pinfunction "IO2_22") (pintype "bidirectional"))
      (node (ref "J4") (pin "4") (pinfunction "4_4") (pintype "passive"))
      (node (ref "R3") (pin "1") (pinfunction "1_1") (pintype "passive"))
    )
    (net (code "52") (name "SCLK") (class "Default")
      (node (ref "IC1") (pin "35") (pinfunction "IO18_35") (pintype "bidirectional"))
      (node (ref "U$9") (pin "1") (pinfunction "SCLK_1") (pintype "bidirectional"))
    )
    (net (code "53") (name "SCL_1") (class "Default")
      (node (ref "IC1") (pin "10") (pinfunction "IO34_10") (pintype "bidirectional"))
      (node (ref "J1") (pin "4") (pinfunction "4_4") (pintype "passive"))
      (node (ref "R5") (pin "1") (pinfunction "1_1") (pintype "passive"))
    )
    (net (code "54") (name "SDA") (class "Default")
      (node (ref "IC1") (pin "21") (pinfunction "IO15_21") (pintype "bidirectional"))
      (node (ref "J4") (pin "3") (pinfunction "3_3") (pintype "passive"))
      (node (ref "R4") (pin "1") (pinfunction "1_1") (pintype "passive"))
    )
    (net (code "55") (name "SDA_1") (class "Default")
      (node (ref "IC1") (pin "11") (pinfunction "IO35_11") (pintype "bidirectional"))
      (node (ref "J1") (pin "3") (pinfunction "3_3") (pintype "passive"))
      (node (ref "R18") (pin "1") (pinfunction "1_1") (pintype "passive"))
    )
    (net (code "56") (name "SENSOR_CAPN") (class "Default")
      (node (ref "IC1") (pin "7") (pinfunction "SENSOR_CAPN_7") (pintype "power_in"))
    )
    (net (code "57") (name "SHLD1") (class "Default")
      (node (ref "SV1") (pin "6") (pinfunction "6_6") (pintype "passive"))
      (node (ref "U$3") (pin "1") (pinfunction "SHLD1_1") (pintype "bidirectional"))
    )
    (net (code "58") (name "SHLD2") (class "Default")
      (node (ref "SV1") (pin "1") (pinfunction "1_1") (pintype "passive"))
      (node (ref "U$3") (pin "6") (pinfunction "SHLD2_6") (pintype "bidirectional"))
    )
    (net (code "59") (name "TXD") (class "Default")
      (node (ref "R12") (pin "2") (pinfunction "2_2") (pintype "passive"))
      (node (ref "U1") (pin "20") (pinfunction "TXD_20") (pintype "bidirectional"))
    )
    (net (code "60") (name "U0RXD") (class "Default")
      (node (ref "IC1") (pin "40") (pinfunction "U0RXD_40") (pintype "bidirectional"))
      (node (ref "R12") (pin "1") (pinfunction "1_1") (pintype "passive"))
    )
    (net (code "61") (name "U0TXD") (class "Default")
      (node (ref "IC1") (pin "41") (pinfunction "U0TXD_41") (pintype "bidirectional"))
      (node (ref "R13") (pin "1") (pinfunction "1_1") (pintype "passive"))
    )
    (net (code "62") (name "VBAT") (class "Default")
      (node (ref "C65") (pin "1") (pinfunction "1_1") (pintype "passive"))
      (node (ref "JP6") (pin "2") (pinfunction "2_2") (pintype "passive"))
      (node (ref "Q2") (pin "3") (pinfunction "D_3") (pintype "passive"))
      (node (ref "R25") (pin "2") (pinfunction "2_2") (pintype "passive"))
      (node (ref "U3") (pin "3") (pinfunction "VBAT_3") (pintype "power_in"))
    )
    (net (code "63") (name "VCC") (class "Default")
      (node (ref "C44") (pin "1") (pinfunction "1_1") (pintype "passive"))
      (node (ref "C83") (pin "1") (pinfunction "1_1") (pintype "passive"))
      (node (ref "R20") (pin "1") (pinfunction "1_1") (pintype "passive"))
      (node (ref "TP41") (pin "TP") (pinfunction "TP_TP") (pintype "input"))
      (node (ref "U$13") (pin "4") (pinfunction "VOUT_4") (pintype "bidirectional"))
      (node (ref "U$15") (pin "5") (pinfunction "EN_5") (pintype "bidirectional"))
      (node (ref "U$15") (pin "8") (pinfunction "IN_8") (pintype "bidirectional"))
    )
    (net (code "64") (name "VIN") (class "Default")
      (node (ref "C1") (pin "1") (pinfunction "1_1") (pintype "passive"))
      (node (ref "C63") (pin "1") (pinfunction "1_1") (pintype "passive"))
      (node (ref "C72") (pin "2") (pinfunction "2_2") (pintype "passive"))
      (node (ref "D1") (pin "C") (pinfunction "C_C") (pintype "passive"))
      (node (ref "Q2") (pin "2") (pinfunction "S_2") (pintype "passive"))
      (node (ref "S2") (pin "3") (pinfunction "S_3") (pintype "passive"))
      (node (ref "U$1") (pin "P$1") (pinfunction "1_P$1") (pintype "passive"))
      (node (ref "U$13") (pin "1") (pinfunction "VIN_1") (pintype "bidirectional"))
      (node (ref "U8") (pin "1") (pinfunction "IN_1") (pintype "input"))
    )
    (net (code "65") (name "VUSB") (class "Default")
      (node (ref "C60") (pin "1") (pinfunction "1_1") (pintype "passive"))
      (node (ref "C61") (pin "1") (pinfunction "1_1") (pintype "passive"))
      (node (ref "C64") (pin "1") (pinfunction "1_1") (pintype "passive"))
      (node (ref "D1") (pin "A") (pinfunction "A_A") (pintype "passive"))
      (node (ref "JP7") (pin "1") (pinfunction "VCC_1") (pintype "bidirectional"))
      (node (ref "Q2") (pin "1") (pinfunction "G_1") (pintype "passive"))
      (node (ref "R16") (pin "1") (pinfunction "1_1") (pintype "passive"))
      (node (ref "R23") (pin "2") (pinfunction "2_2") (pintype "passive"))
      (node (ref "U1") (pin "15") (pinfunction "VCC_15") (pintype "bidirectional"))
      (node (ref "U3") (pin "4") (pinfunction "VIN_4") (pintype "power_in"))
    )
    (net (code "66") (name "unconnected-(IC1A-CAP1_NC-Pad48)") (class "Default")
      (node (ref "IC1") (pin "48") (pinfunction "CAP1_NC_48") (pintype "bidirectional"))
    )
    (net (code "67") (name "unconnected-(IC1A-CAP2_NC-Pad47)") (class "Default")
      (node (ref "IC1") (pin "47") (pinfunction "CAP2_NC_47") (pintype "bidirectional"))
    )
    (net (code "68") (name "unconnected-(IC1A-CLK-Pad31)") (class "Default")
      (node (ref "IC1") (pin "31") (pinfunction "CLK_31") (pintype "bidirectional"))
    )
    (net (code "69") (name "unconnected-(IC1A-CMD-Pad30)") (class "Default")
      (node (ref "IC1") (pin "30") (pinfunction "CMD_30") (pintype "bidirectional"))
    )
    (net (code "70") (name "unconnected-(IC1A-IO13-Pad20)") (class "Default")
      (node (ref "IC1") (pin "20") (pinfunction "IO13_20") (pintype "bidirectional"))
    )
    (net (code "71") (name "unconnected-(IC1A-IO14-Pad17)") (class "Default")
      (node (ref "IC1") (pin "17") (pinfunction "IO14_17") (pintype "bidirectional"))
    )
    (net (code "72") (name "unconnected-(IC1A-IO25-Pad14)") (class "Default")
      (node (ref "IC1") (pin "14") (pinfunction "IO25_14") (pintype "bidirectional"))
    )
    (net (code "73") (name "unconnected-(IC1A-SD0-Pad32)") (class "Default")
      (node (ref "IC1") (pin "32") (pinfunction "SD0_32") (pintype "bidirectional"))
    )
    (net (code "74") (name "unconnected-(IC1A-SD1-Pad33)") (class "Default")
      (node (ref "IC1") (pin "33") (pinfunction "SD1_33") (pintype "bidirectional"))
    )
    (net (code "75") (name "unconnected-(IC1A-SD2-Pad28)") (class "Default")
      (node (ref "IC1") (pin "28") (pinfunction "SD2_28") (pintype "bidirectional"))
    )
    (net (code "76") (name "unconnected-(IC1A-SD3-Pad29)") (class "Default")
      (node (ref "IC1") (pin "29") (pinfunction "SD3_29") (pintype "bidirectional"))
    )
    (net (code "77") (name "unconnected-(IC1A-SENSOR_CAPP-Pad6)") (class "Default")
      (node (ref "IC1") (pin "6") (pinfunction "SENSOR_CAPP_6") (pintype "bidirectional"))
    )
    (net (code "78") (name "unconnected-(IC1A-SENSOR_VN-Pad8)") (class "Default")
      (node (ref "IC1") (pin "8") (pinfunction "SENSOR_VN_8") (pintype "bidirectional"))
    )
    (net (code "79") (name "unconnected-(IC1A-VDD_SDIO_NC-Pad26)") (class "Default")
      (node (ref "IC1") (pin "26") (pinfunction "VDD_SDIO_NC_26") (pintype "bidirectional"))
    )
    (net (code "80") (name "unconnected-(IC1A-XTAL_N_NC-Pad44)") (class "Default")
      (node (ref "IC1") (pin "44") (pinfunction "XTAL_N_NC_44") (pintype "bidirectional"))
    )
    (net (code "81") (name "unconnected-(IC1A-XTAL_P_NC-Pad45)") (class "Default")
      (node (ref "IC1") (pin "45") (pinfunction "XTAL_P_NC_45") (pintype "bidirectional"))
    )
    (net (code "82") (name "unconnected-(JP7-ID-Pad4)") (class "Default")
      (node (ref "JP7") (pin "4") (pinfunction "ID_4") (pintype "bidirectional"))
    )
    (net (code "83") (name "unconnected-(SV3-Pad7)") (class "Default")
      (node (ref "SV3") (pin "7") (pinfunction "7_7") (pintype "passive"))
    )
    (net (code "84") (name "unconnected-(SW2-P1-PadA')") (class "Default")
      (node (ref "SW2") (pin "A'") (pinfunction "P1_A'") (pintype "passive"))
    )
    (net (code "85") (name "unconnected-(TP3-PadTP)") (class "Default")
      (node (ref "TP3") (pin "TP") (pinfunction "TP_TP") (pintype "input"))
    )
    (net (code "86") (name "unconnected-(TP5-PadTP)") (class "Default")
      (node (ref "TP5") (pin "TP") (pinfunction "TP_TP") (pintype "input"))
    )
    (net (code "87") (name "unconnected-(TP6-PadTP)") (class "Default")
      (node (ref "TP6") (pin "TP") (pinfunction "TP_TP") (pintype "input"))
    )
    (net (code "88") (name "unconnected-(TP7-PadTP)") (class "Default")
      (node (ref "TP7") (pin "TP") (pinfunction "TP_TP") (pintype "input"))
    )
    (net (code "89") (name "unconnected-(TP8-PadTP)") (class "Default")
      (node (ref "TP8") (pin "TP") (pinfunction "TP_TP") (pintype "input"))
    )
    (net (code "90") (name "unconnected-(TP9-PadTP)") (class "Default")
      (node (ref "TP9") (pin "TP") (pinfunction "TP_TP") (pintype "input"))
    )
    (net (code "91") (name "unconnected-(TP11-PadTP)") (class "Default")
      (node (ref "TP11") (pin "TP") (pinfunction "TP_TP") (pintype "input"))
    )
    (net (code "92") (name "unconnected-(TP12-PadTP)") (class "Default")
      (node (ref "TP12") (pin "TP") (pinfunction "TP_TP") (pintype "input"))
    )
    (net (code "93") (name "unconnected-(TP13-PadTP)") (class "Default")
      (node (ref "TP13") (pin "TP") (pinfunction "TP_TP") (pintype "input"))
    )
    (net (code "94") (name "unconnected-(TP14-PadTP)") (class "Default")
      (node (ref "TP14") (pin "TP") (pinfunction "TP_TP") (pintype "input"))
    )
    (net (code "95") (name "unconnected-(TP15-PadTP)") (class "Default")
      (node (ref "TP15") (pin "TP") (pinfunction "TP_TP") (pintype "input"))
    )
    (net (code "96") (name "unconnected-(TP16-PadTP)") (class "Default")
      (node (ref "TP16") (pin "TP") (pinfunction "TP_TP") (pintype "input"))
    )
    (net (code "97") (name "unconnected-(TP17-PadTP)") (class "Default")
      (node (ref "TP17") (pin "TP") (pinfunction "TP_TP") (pintype "input"))
    )
    (net (code "98") (name "unconnected-(TP18-PadTP)") (class "Default")
      (node (ref "TP18") (pin "TP") (pinfunction "TP_TP") (pintype "input"))
    )
    (net (code "99") (name "unconnected-(TP19-PadTP)") (class "Default")
      (node (ref "TP19") (pin "TP") (pinfunction "TP_TP") (pintype "input"))
    )
    (net (code "100") (name "unconnected-(TP20-PadTP)") (class "Default")
      (node (ref "TP20") (pin "TP") (pinfunction "TP_TP") (pintype "input"))
    )
    (net (code "101") (name "unconnected-(TP21-PadTP)") (class "Default")
      (node (ref "TP21") (pin "TP") (pinfunction "TP_TP") (pintype "input"))
    )
    (net (code "102") (name "unconnected-(TP22-PadTP)") (class "Default")
      (node (ref "TP22") (pin "TP") (pinfunction "TP_TP") (pintype "input"))
    )
    (net (code "103") (name "unconnected-(TP23-PadTP)") (class "Default")
      (node (ref "TP23") (pin "TP") (pinfunction "TP_TP") (pintype "input"))
    )
    (net (code "104") (name "unconnected-(TP24-PadTP)") (class "Default")
      (node (ref "TP24") (pin "TP") (pinfunction "TP_TP") (pintype "input"))
    )
    (net (code "105") (name "unconnected-(TP25-PadTP)") (class "Default")
      (node (ref "TP25") (pin "TP") (pinfunction "TP_TP") (pintype "input"))
    )
    (net (code "106") (name "unconnected-(TP26-PadTP)") (class "Default")
      (node (ref "TP26") (pin "TP") (pinfunction "TP_TP") (pintype "input"))
    )
    (net (code "107") (name "unconnected-(TP27-PadTP)") (class "Default")
      (node (ref "TP27") (pin "TP") (pinfunction "TP_TP") (pintype "input"))
    )
    (net (code "108") (name "unconnected-(TP28-PadTP)") (class "Default")
      (node (ref "TP28") (pin "TP") (pinfunction "TP_TP") (pintype "input"))
    )
    (net (code "109") (name "unconnected-(TP29-PadTP)") (class "Default")
      (node (ref "TP29") (pin "TP") (pinfunction "TP_TP") (pintype "input"))
    )
    (net (code "110") (name "unconnected-(TP30-PadTP)") (class "Default")
      (node (ref "TP30") (pin "TP") (pinfunction "TP_TP") (pintype "input"))
    )
    (net (code "111") (name "unconnected-(TP31-PadTP)") (class "Default")
      (node (ref "TP31") (pin "TP") (pinfunction "TP_TP") (pintype "input"))
    )
    (net (code "112") (name "unconnected-(TP32-PadTP)") (class "Default")
      (node (ref "TP32") (pin "TP") (pinfunction "TP_TP") (pintype "input"))
    )
    (net (code "113") (name "unconnected-(TP33-PadTP)") (class "Default")
      (node (ref "TP33") (pin "TP") (pinfunction "TP_TP") (pintype "input"))
    )
    (net (code "114") (name "unconnected-(TP34-PadTP)") (class "Default")
      (node (ref "TP34") (pin "TP") (pinfunction "TP_TP") (pintype "input"))
    )
    (net (code "115") (name "unconnected-(TP35-PadTP)") (class "Default")
      (node (ref "TP35") (pin "TP") (pinfunction "TP_TP") (pintype "input"))
    )
    (net (code "116") (name "unconnected-(TP36-PadTP)") (class "Default")
      (node (ref "TP36") (pin "TP") (pinfunction "TP_TP") (pintype "input"))
    )
    (net (code "117") (name "unconnected-(TP37-PadTP)") (class "Default")
      (node (ref "TP37") (pin "TP") (pinfunction "TP_TP") (pintype "input"))
    )
    (net (code "118") (name "unconnected-(TP38-PadTP)") (class "Default")
      (node (ref "TP38") (pin "TP") (pinfunction "TP_TP") (pintype "input"))
    )
    (net (code "119") (name "unconnected-(TP39-PadTP)") (class "Default")
      (node (ref "TP39") (pin "TP") (pinfunction "TP_TP") (pintype "input"))
    )
    (net (code "120") (name "unconnected-(TP40-PadTP)") (class "Default")
      (node (ref "TP40") (pin "TP") (pinfunction "TP_TP") (pintype "input"))
    )
    (net (code "121") (name "unconnected-(TP42-PadTP)") (class "Default")
      (node (ref "TP42") (pin "TP") (pinfunction "TP_TP") (pintype "input"))
    )
    (net (code "122") (name "unconnected-(TP43-PadTP)") (class "Default")
      (node (ref "TP43") (pin "TP") (pinfunction "TP_TP") (pintype "input"))
    )
    (net (code "123") (name "unconnected-(TP44-PadTP)") (class "Default")
      (node (ref "TP44") (pin "TP") (pinfunction "TP_TP") (pintype "input"))
    )
    (net (code "124") (name "unconnected-(TP45-PadTP)") (class "Default")
      (node (ref "TP45") (pin "TP") (pinfunction "TP_TP") (pintype "input"))
    )
    (net (code "125") (name "unconnected-(TP46-PadTP)") (class "Default")
      (node (ref "TP46") (pin "TP") (pinfunction "TP_TP") (pintype "input"))
    )
    (net (code "126") (name "unconnected-(TP47-PadTP)") (class "Default")
      (node (ref "TP47") (pin "TP") (pinfunction "TP_TP") (pintype "input"))
    )
    (net (code "127") (name "unconnected-(TP48-PadTP)") (class "Default")
      (node (ref "TP48") (pin "TP") (pinfunction "TP_TP") (pintype "input"))
    )
    (net (code "128") (name "unconnected-(TP50-PadTP)") (class "Default")
      (node (ref "TP50") (pin "TP") (pinfunction "TP_TP") (pintype "input"))
    )
    (net (code "129") (name "unconnected-(TP51-PadTP)") (class "Default")
      (node (ref "TP51") (pin "TP") (pinfunction "TP_TP") (pintype "input"))
    )
    (net (code "130") (name "unconnected-(TP52-PadTP)") (class "Default")
      (node (ref "TP52") (pin "TP") (pinfunction "TP_TP") (pintype "input"))
    )
    (net (code "131") (name "unconnected-(TP53-PadTP)") (class "Default")
      (node (ref "TP53") (pin "TP") (pinfunction "TP_TP") (pintype "input"))
    )
    (net (code "132") (name "unconnected-(TP54-PadTP)") (class "Default")
      (node (ref "TP54") (pin "TP") (pinfunction "TP_TP") (pintype "input"))
    )
    (net (code "133") (name "unconnected-(TP55-PadTP)") (class "Default")
      (node (ref "TP55") (pin "TP") (pinfunction "TP_TP") (pintype "input"))
    )
    (net (code "134") (name "unconnected-(TP56-PadTP)") (class "Default")
      (node (ref "TP56") (pin "TP") (pinfunction "TP_TP") (pintype "input"))
    )
    (net (code "135") (name "unconnected-(TP58-PadTP)") (class "Default")
      (node (ref "TP58") (pin "TP") (pinfunction "TP_TP") (pintype "input"))
    )
    (net (code "136") (name "unconnected-(TP59-PadTP)") (class "Default")
      (node (ref "TP59") (pin "TP") (pinfunction "TP_TP") (pintype "input"))
    )
    (net (code "137") (name "unconnected-(TP60-PadTP)") (class "Default")
      (node (ref "TP60") (pin "TP") (pinfunction "TP_TP") (pintype "input"))
    )
    (net (code "138") (name "unconnected-(TP62-PadTP)") (class "Default")
      (node (ref "TP62") (pin "TP") (pinfunction "TP_TP") (pintype "input"))
    )
    (net (code "139") (name "unconnected-(TP63-PadTP)") (class "Default")
      (node (ref "TP63") (pin "TP") (pinfunction "TP_TP") (pintype "input"))
    )
    (net (code "140") (name "unconnected-(TP65-PadTP)") (class "Default")
      (node (ref "TP65") (pin "TP") (pinfunction "TP_TP") (pintype "input"))
    )
    (net (code "141") (name "unconnected-(TP66-PadTP)") (class "Default")
      (node (ref "TP66") (pin "TP") (pinfunction "TP_TP") (pintype "input"))
    )
    (net (code "142") (name "unconnected-(TP68-PadTP)") (class "Default")
      (node (ref "TP68") (pin "TP") (pinfunction "TP_TP") (pintype "input"))
    )
    (net (code "143") (name "unconnected-(TP69-PadTP)") (class "Default")
      (node (ref "TP69") (pin "TP") (pinfunction "TP_TP") (pintype "input"))
    )
    (net (code "144") (name "unconnected-(TP70-PadTP)") (class "Default")
      (node (ref "TP70") (pin "TP") (pinfunction "TP_TP") (pintype "input"))
    )
    (net (code "145") (name "unconnected-(TP71-PadTP)") (class "Default")
      (node (ref "TP71") (pin "TP") (pinfunction "TP_TP") (pintype "input"))
    )
    (net (code "146") (name "unconnected-(TP72-PadTP)") (class "Default")
      (node (ref "TP72") (pin "TP") (pinfunction "TP_TP") (pintype "input"))
    )
    (net (code "147") (name "unconnected-(TP73-PadTP)") (class "Default")
      (node (ref "TP73") (pin "TP") (pinfunction "TP_TP") (pintype "input"))
    )
    (net (code "148") (name "unconnected-(TP74-PadTP)") (class "Default")
      (node (ref "TP74") (pin "TP") (pinfunction "TP_TP") (pintype "input"))
    )
    (net (code "149") (name "unconnected-(U1-CBUS0-Pad18)") (class "Default")
      (node (ref "U1") (pin "18") (pinfunction "CBUS0_18") (pintype "bidirectional"))
    )
    (net (code "150") (name "unconnected-(U1-CBUS1-Pad17)") (class "Default")
      (node (ref "U1") (pin "17") (pinfunction "CBUS1_17") (pintype "bidirectional"))
    )
    (net (code "151") (name "unconnected-(U1-CBUS2-Pad10)") (class "Default")
      (node (ref "U1") (pin "10") (pinfunction "CBUS2_10") (pintype "bidirectional"))
    )
    (net (code "152") (name "unconnected-(U1-CBUS3-Pad19)") (class "Default")
      (node (ref "U1") (pin "19") (pinfunction "CBUS3_19") (pintype "bidirectional"))
    )
    (net (code "153") (name "unconnected-(U1-~{CTS}-Pad9)") (class "Default")
      (node (ref "U1") (pin "9") (pinfunction "~{CTS}_9") (pintype "bidirectional"))
    )
    (net (code "154") (name "unconnected-(U1-~{DCD}-Pad8)") (class "Default")
      (node (ref "U1") (pin "8") (pinfunction "~{DCD}_8") (pintype "bidirectional"))
    )
    (net (code "155") (name "unconnected-(U1-~{DSR}-Pad7)") (class "Default")
      (node (ref "U1") (pin "7") (pinfunction "~{DSR}_7") (pintype "bidirectional"))
    )
    (net (code "156") (name "unconnected-(U1-~{RI}-Pad5)") (class "Default")
      (node (ref "U1") (pin "5") (pinfunction "~{RI}_5") (pintype "bidirectional"))
    )
    (net (code "157") (name "unconnected-(U8-BP-Pad4)") (class "Default")
      (node (ref "U8") (pin "4") (pinfunction "BP_4") (pintype "input"))
    )
    (net (code "158") (name "~{CS1}") (class "Default")
      (node (ref "IC1") (pin "27") (pinfunction "IO17_27") (pintype "bidirectional"))
      (node (ref "U$9") (pin "2") (pinfunction "~{CS}_2") (pintype "bidirectional"))
    )
    (net (code "159") (name "~{DRDY}") (class "Default")
      (node (ref "IC1") (pin "25") (pinfunction "IO16_25") (pintype "bidirectional"))
      (node (ref "U$9") (pin "14") (pinfunction "~{DRDY}_14") (pintype "bidirectional"))
    )
  )
)
